# design.net
KiCad netlist of a schematic drawn in Altium Designer
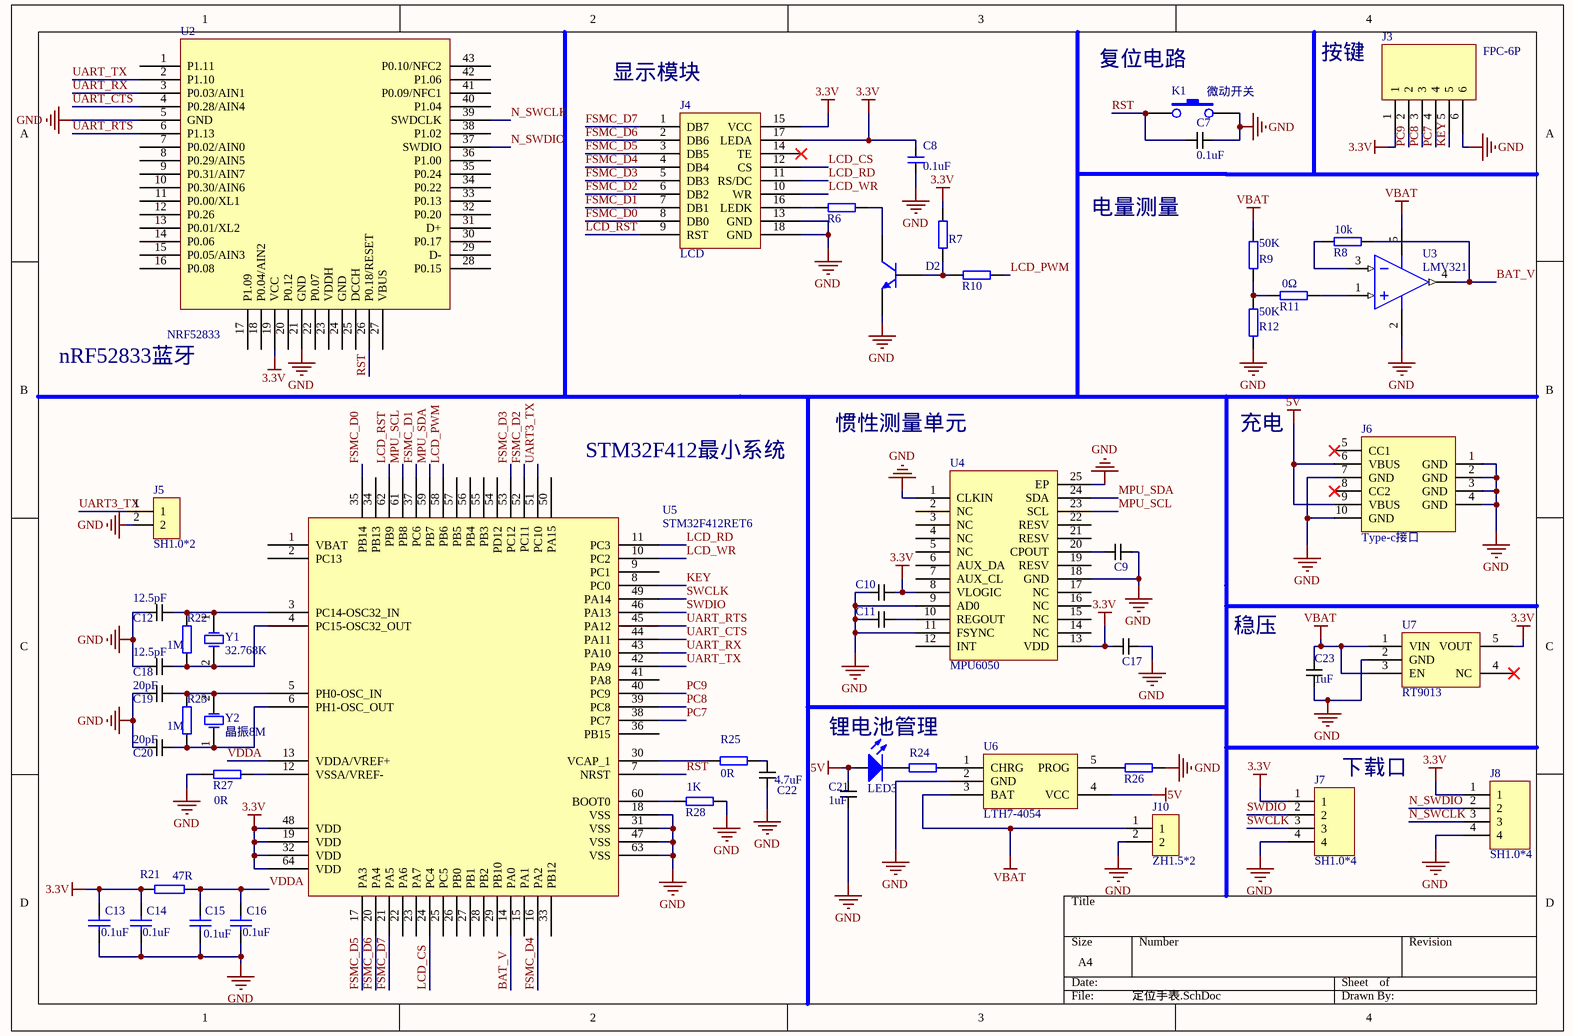
[diagram p0: 定位手表.SchDoc]

(export (version "E")
  (design (tool "Eeschema 10.0.6"))
  (components
    (comp (ref "C7")
      (value "0.1uF")
      (footprint "0402-CAP")
      (description "无极性贴片电容")
      (libsource (lib "定位手表") (part "电容"))
    )
    (comp (ref "C8")
      (value "0.1uF")
      (footprint "0402-CAP")
      (description "无极性贴片电容")
      (libsource (lib "定位手表") (part "电容"))
    )
    (comp (ref "C9")
      (value "2.2nF")
      (footprint "0402-CAP")
      (description "无极性贴片电容")
      (libsource (lib "定位手表") (part "电容"))
    )
    (comp (ref "C10")
      (value "0.1uF")
      (footprint "0402-CAP")
      (description "无极性贴片电容")
      (libsource (lib "定位手表") (part "电容"))
    )
    (comp (ref "C11")
      (value "0.1uF")
      (footprint "0402-CAP")
      (description "无极性贴片电容")
      (libsource (lib "定位手表") (part "电容"))
    )
    (comp (ref "C12")
      (value "12.5pF")
      (footprint "0402-CAP")
      (description "无极性贴片电容")
      (libsource (lib "定位手表") (part "电容"))
    )
    (comp (ref "C13") (value "0.1uF") (footprint "0402-CAP") (libsource (lib "定位手表") (part "cap")))
    (comp (ref "C14") (value "0.1uF") (footprint "0402-CAP") (libsource (lib "定位手表") (part "cap")))
    (comp (ref "C15") (value "0.1uF") (footprint "0402-CAP") (libsource (lib "定位手表") (part "cap")))
    (comp (ref "C16") (value "0.1uF") (footprint "0402-CAP") (libsource (lib "定位手表") (part "cap")))
    (comp (ref "C17")
      (value "0.1uF")
      (footprint "0402-CAP")
      (description "无极性贴片电容")
      (libsource (lib "定位手表") (part "电容"))
    )
    (comp (ref "C18")
      (value "12.5pF")
      (footprint "0402-CAP")
      (description "无极性贴片电容")
      (libsource (lib "定位手表") (part "电容"))
    )
    (comp (ref "C19")
      (value "20pF")
      (footprint "0402-CAP")
      (description "无极性贴片电容")
      (libsource (lib "定位手表") (part "电容"))
    )
    (comp (ref "C20")
      (value "20pF")
      (footprint "0402-CAP")
      (description "无极性贴片电容")
      (libsource (lib "定位手表") (part "电容"))
    )
    (comp (ref "C21")
      (value "1uF")
      (footprint "0402-CAP")
      (description "无极性贴片电容")
      (libsource (lib "定位手表") (part "电容"))
    )
    (comp (ref "C22")
      (value "4.7uF")
      (footprint "0603-CAP")
      (description "无极性贴片电容")
      (libsource (lib "定位手表") (part "电容"))
    )
    (comp (ref "C23")
      (value "1uF")
      (footprint "0402-CAP")
      (description "无极性贴片电容")
      (libsource (lib "定位手表") (part "电容"))
    )
    (comp (ref "D2") (value "三极管") (footprint "SOT23-3M") (libsource (lib "定位手表") (part "三极管")))
    (comp (ref "J3") (value "FPC-6P") (footprint "FPC0.5-WT-6P") (libsource (lib "定位手表") (part "FPC-6P")))
    (comp (ref "J4") (value "LCD") (footprint "LCD") (libsource (lib "定位手表") (part "LCD")))
    (comp (ref "J5") (value "SH1.0*2") (footprint "SH1.0-WT-2P") (libsource (lib "定位手表") (part "SH1.0*2")))
    (comp (ref "J6")
      (value "Type-c接口")
      (footprint "type-c")
      (description "接口")
      (libsource (lib "定位手表") (part "Type-c接口"))
    )
    (comp (ref "J7") (value "SH1.0*4") (footprint "SH1.0-WT-4P") (libsource (lib "定位手表") (part "SH1.0*4")))
    (comp (ref "J8") (value "SH1.0*4") (footprint "SH1.0-WT-4P") (libsource (lib "定位手表") (part "SH1.0*4")))
    (comp (ref "J10") (value "ZH1.5*2") (footprint "ZH1.5-WS-2P") (libsource (lib "定位手表") (part "ZH1.5*2")))
    (comp (ref "K1") (value "微动开关") (footprint "轻触开关") (libsource (lib "定位手表") (part "微动开关")))
    (comp (ref "LED3") (value "发光二极管") (footprint "0603-LED") (libsource (lib "定位手表") (part "发光二极管")))
    (comp (ref "R6")
      (value "10R")
      (footprint "0402-RES")
      (description "电阻")
      (libsource (lib "定位手表") (part "电阻"))
    )
    (comp (ref "R7")
      (value "10K")
      (footprint "0402-RES")
      (description "电阻")
      (libsource (lib "定位手表") (part "电阻"))
    )
    (comp (ref "R8")
      (value "10k")
      (footprint "0402-RES")
      (description "电阻")
      (libsource (lib "智能门锁") (part "电阻"))
    )
    (comp (ref "R9")
      (value "50K")
      (footprint "0402-RES")
      (description "电阻")
      (libsource (lib "智能门锁") (part "电阻"))
    )
    (comp (ref "R10")
      (value "1K")
      (footprint "0402-RES")
      (description "电阻")
      (libsource (lib "定位手表") (part "电阻"))
    )
    (comp (ref "R11")
      (value "0Ω")
      (footprint "0402-RES")
      (description "电阻")
      (libsource (lib "智能门锁") (part "电阻"))
    )
    (comp (ref "R12")
      (value "50K")
      (footprint "0402-RES")
      (description "电阻")
      (libsource (lib "智能门锁") (part "电阻"))
    )
    (comp (ref "R21") (value "47R") (footprint "0402-RES") (libsource (lib "定位手表") (part "RES")))
    (comp (ref "R22")
      (value "1M")
      (footprint "0402-RES")
      (description "电阻")
      (libsource (lib "定位手表") (part "电阻"))
    )
    (comp (ref "R23")
      (value "1M")
      (footprint "0402-RES")
      (description "电阻")
      (libsource (lib "定位手表") (part "电阻"))
    )
    (comp (ref "R24")
      (value "10K")
      (footprint "0402-RES")
      (description "电阻")
      (libsource (lib "定位手表") (part "电阻"))
    )
    (comp (ref "R25")
      (value "0R")
      (footprint "0402-RES")
      (description "电阻")
      (libsource (lib "定位手表") (part "电阻"))
    )
    (comp (ref "R26")
      (value "1.65K")
      (footprint "0402-RES")
      (description "电阻")
      (libsource (lib "定位手表") (part "电阻"))
    )
    (comp (ref "R27")
      (value "0R")
      (footprint "0402-RES")
      (description "电阻")
      (libsource (lib "定位手表") (part "电阻"))
    )
    (comp (ref "R28")
      (value "1K")
      (footprint "0402-RES")
      (description "电阻")
      (libsource (lib "定位手表") (part "电阻"))
    )
    (comp (ref "U2") (value "NRF52833") (footprint "nrf52833") (libsource (lib "定位手表") (part "NRF52833")))
    (comp (ref "U3") (value "LMV321") (footprint "SOT23-5") (libsource (lib "定位手表") (part "LMV321")))
    (comp (ref "U4") (value "MPU6050") (footprint "MPU6050") (libsource (lib "定位手表") (part "MPU6050")))
    (comp (ref "U5")
      (value "STM32F412RET6")
      (footprint "STM32F412RET6")
      (libsource (lib "定位手表") (part "STM32F412RET6"))
    )
    (comp (ref "U6") (value "LTH7-4054") (footprint "SOT23-5") (libsource (lib "定位手表") (part "LTH7-4054")))
    (comp (ref "U7") (value "RT9013") (footprint "SOT23-5") (libsource (lib "定位手表") (part "RT9013")))
    (comp (ref "Y1") (value "32.768K") (footprint "晶振32.768K") (libsource (lib "定位手表") (part "32.768K")))
    (comp (ref "Y2") (value "晶振8M") (footprint "晶振8M") (libsource (lib "定位手表") (part "晶振8M")))
  )
  (nets
    (net (code "1") (name "/BAT_V") (class "Default")
      (node (ref "R8") (pin "2") (pinfunction "2_2") (pintype "passive"))
      (node (ref "U3") (pin "4") (pinfunction "4_4") (pintype "output"))
      (node (ref "U5") (pin "14") (pinfunction "PA0_14") (pintype "passive"))
    )
    (net (code "2") (name "/FSMC_D0") (class "Default")
      (node (ref "J4") (pin "8") (pinfunction "DB0_8") (pintype "passive"))
      (node (ref "U5") (pin "35") (pinfunction "PB14_35") (pintype "passive"))
    )
    (net (code "3") (name "/FSMC_D1") (class "Default")
      (node (ref "J4") (pin "7") (pinfunction "DB1_7") (pintype "passive"))
      (node (ref "U5") (pin "37") (pinfunction "PC6_37") (pintype "passive"))
    )
    (net (code "4") (name "/FSMC_D2") (class "Default")
      (node (ref "J4") (pin "6") (pinfunction "DB2_6") (pintype "passive"))
      (node (ref "U5") (pin "52") (pinfunction "PC11_52") (pintype "passive"))
    )
    (net (code "5") (name "/FSMC_D3") (class "Default")
      (node (ref "J4") (pin "5") (pinfunction "DB3_5") (pintype "passive"))
      (node (ref "U5") (pin "53") (pinfunction "PC12_53") (pintype "passive"))
    )
    (net (code "6") (name "/FSMC_D4") (class "Default")
      (node (ref "J4") (pin "4") (pinfunction "DB4_4") (pintype "passive"))
      (node (ref "U5") (pin "16") (pinfunction "PA2_16") (pintype "passive"))
    )
    (net (code "7") (name "/FSMC_D5") (class "Default")
      (node (ref "J4") (pin "3") (pinfunction "DB5_3") (pintype "passive"))
      (node (ref "U5") (pin "17") (pinfunction "PA3_17") (pintype "passive"))
    )
    (net (code "8") (name "/FSMC_D6") (class "Default")
      (node (ref "J4") (pin "2") (pinfunction "DB6_2") (pintype "passive"))
      (node (ref "U5") (pin "20") (pinfunction "PA4_20") (pintype "passive"))
    )
    (net (code "9") (name "/FSMC_D7") (class "Default")
      (node (ref "J4") (pin "1") (pinfunction "DB7_1") (pintype "passive"))
      (node (ref "U5") (pin "21") (pinfunction "PA5_21") (pintype "passive"))
    )
    (net (code "10") (name "/KEY") (class "Default")
      (node (ref "J3") (pin "5") (pinfunction "5_5") (pintype "passive"))
      (node (ref "U5") (pin "8") (pinfunction "PC0_8") (pintype "passive"))
    )
    (net (code "11") (name "/LCD_CS") (class "Default")
      (node (ref "J4") (pin "12") (pinfunction "CS_12") (pintype "passive"))
      (node (ref "U5") (pin "24") (pinfunction "PC4_24") (pintype "passive"))
    )
    (net (code "12") (name "/LCD_PWM") (class "Default")
      (node (ref "R10") (pin "2") (pinfunction "2_2") (pintype "passive"))
      (node (ref "U5") (pin "58") (pinfunction "PB6_58") (pintype "passive"))
    )
    (net (code "13") (name "/LCD_RD") (class "Default")
      (node (ref "J4") (pin "11") (pinfunction "RS/DC_11") (pintype "passive"))
      (node (ref "U5") (pin "11") (pinfunction "PC3_11") (pintype "passive"))
    )
    (net (code "14") (name "/LCD_RST") (class "Default")
      (node (ref "J4") (pin "9") (pinfunction "RST_9") (pintype "passive"))
      (node (ref "U5") (pin "62") (pinfunction "PB9_62") (pintype "passive"))
    )
    (net (code "15") (name "/LCD_WR") (class "Default")
      (node (ref "J4") (pin "10") (pinfunction "WR_10") (pintype "passive"))
      (node (ref "U5") (pin "10") (pinfunction "PC2_10") (pintype "passive"))
    )
    (net (code "16") (name "/MPU_SCL") (class "Default")
      (node (ref "U4") (pin "23") (pinfunction "SCL_23") (pintype "passive"))
      (node (ref "U5") (pin "61") (pinfunction "PB8_61") (pintype "passive"))
    )
    (net (code "17") (name "/MPU_SDA") (class "Default")
      (node (ref "U4") (pin "24") (pinfunction "SDA_24") (pintype "passive"))
      (node (ref "U5") (pin "59") (pinfunction "PB7_59") (pintype "passive"))
    )
    (net (code "18") (name "/N_SWCLK") (class "Default")
      (node (ref "J8") (pin "3") (pinfunction "3_3") (pintype "passive"))
      (node (ref "U2") (pin "39") (pinfunction "SWDCLK_39") (pintype "passive"))
    )
    (net (code "19") (name "/N_SWDIO") (class "Default")
      (node (ref "J8") (pin "2") (pinfunction "2_2") (pintype "passive"))
      (node (ref "U2") (pin "37") (pinfunction "SWDIO_37") (pintype "passive"))
    )
    (net (code "20") (name "/PC7") (class "Default")
      (node (ref "J3") (pin "4") (pinfunction "4_4") (pintype "passive"))
      (node (ref "U5") (pin "38") (pinfunction "PC7_38") (pintype "passive"))
    )
    (net (code "21") (name "/PC8") (class "Default")
      (node (ref "J3") (pin "3") (pinfunction "3_3") (pintype "passive"))
      (node (ref "U5") (pin "39") (pinfunction "PC8_39") (pintype "passive"))
    )
    (net (code "22") (name "/PC9") (class "Default")
      (node (ref "J3") (pin "2") (pinfunction "2_2") (pintype "passive"))
      (node (ref "U5") (pin "40") (pinfunction "PC9_40") (pintype "passive"))
    )
    (net (code "23") (name "/RST") (class "Default")
      (node (ref "C7") (pin "2") (pintype "passive"))
      (node (ref "K1") (pin "1") (pinfunction "1_1") (pintype "passive"))
      (node (ref "U2") (pin "26") (pinfunction "P0.18/RESET_26") (pintype "passive"))
      (node (ref "U5") (pin "7") (pinfunction "NRST_7") (pintype "passive"))
    )
    (net (code "24") (name "/SWCLK") (class "Default")
      (node (ref "J7") (pin "3") (pinfunction "3_3") (pintype "passive"))
      (node (ref "U5") (pin "49") (pinfunction "PA14_49") (pintype "passive"))
    )
    (net (code "25") (name "/SWDIO") (class "Default")
      (node (ref "J7") (pin "2") (pinfunction "2_2") (pintype "passive"))
      (node (ref "U5") (pin "46") (pinfunction "PA13_46") (pintype "passive"))
    )
    (net (code "26") (name "/UART3_TX") (class "Default")
      (node (ref "J5") (pin "1") (pinfunction "1_1") (pintype "passive"))
      (node (ref "U5") (pin "51") (pinfunction "PC10_51") (pintype "passive"))
    )
    (net (code "27") (name "/UART_CTS") (class "Default")
      (node (ref "U2") (pin "4") (pinfunction "P0.28/AIN4_4") (pintype "passive"))
      (node (ref "U5") (pin "44") (pinfunction "PA11_44") (pintype "passive"))
    )
    (net (code "28") (name "/UART_RTS") (class "Default")
      (node (ref "U2") (pin "6") (pinfunction "P1.13_6") (pintype "passive"))
      (node (ref "U5") (pin "45") (pinfunction "PA12_45") (pintype "passive"))
    )
    (net (code "29") (name "/UART_RX") (class "Default")
      (node (ref "U2") (pin "3") (pinfunction "P0.03/AIN1_3") (pintype "passive"))
      (node (ref "U5") (pin "43") (pinfunction "PA10_43") (pintype "passive"))
    )
    (net (code "30") (name "/UART_TX") (class "Default")
      (node (ref "U2") (pin "2") (pinfunction "P1.10_2") (pintype "passive"))
      (node (ref "U5") (pin "42") (pinfunction "PA9_42") (pintype "passive"))
    )
    (net (code "31") (name "/VDDA") (class "Default")
      (node (ref "C15") (pin "2") (pinfunction "2_2") (pintype "passive"))
      (node (ref "C16") (pin "2") (pinfunction "2_2") (pintype "passive"))
      (node (ref "R21") (pin "2") (pinfunction "2_2") (pintype "passive"))
      (node (ref "U5") (pin "13") (pinfunction "VDDA/VREF+_13") (pintype "passive"))
    )
    (net (code "32") (name "3.3V") (class "Default")
      (node (ref "C10") (pin "2") (pintype "passive"))
      (node (ref "C13") (pin "2") (pinfunction "2_2") (pintype "passive"))
      (node (ref "C14") (pin "2") (pinfunction "2_2") (pintype "passive"))
      (node (ref "C17") (pin "2") (pintype "passive"))
      (node (ref "C8") (pin "1") (pintype "passive"))
      (node (ref "J3") (pin "1") (pinfunction "1_1") (pintype "passive"))
      (node (ref "J4") (pin "15") (pinfunction "VCC_15") (pintype "passive"))
      (node (ref "J4") (pin "17") (pinfunction "LEDA_17") (pintype "passive"))
      (node (ref "J7") (pin "1") (pinfunction "1_1") (pintype "passive"))
      (node (ref "J8") (pin "1") (pinfunction "1_1") (pintype "passive"))
      (node (ref "R21") (pin "1") (pinfunction "1_1") (pintype "passive"))
      (node (ref "R7") (pin "2") (pinfunction "2_2") (pintype "passive"))
      (node (ref "U2") (pin "19") (pinfunction "VCC_19") (pintype "passive"))
      (node (ref "U4") (pin "13") (pinfunction "VDD_13") (pintype "passive"))
      (node (ref "U4") (pin "8") (pinfunction "VLOGIC_8") (pintype "passive"))
      (node (ref "U5") (pin "19") (pinfunction "VDD_19") (pintype "passive"))
      (node (ref "U5") (pin "32") (pinfunction "VDD_32") (pintype "passive"))
      (node (ref "U5") (pin "48") (pinfunction "VDD_48") (pintype "passive"))
      (node (ref "U5") (pin "64") (pinfunction "VDD_64") (pintype "passive"))
      (node (ref "U7") (pin "5") (pinfunction "VOUT_5") (pintype "passive"))
    )
    (net (code "33") (name "5V") (class "Default")
      (node (ref "C21") (pin "1") (pintype "passive"))
      (node (ref "J6") (pin "6") (pinfunction "VBUS_6") (pintype "passive"))
      (node (ref "J6") (pin "9") (pinfunction "VBUS_9") (pintype "passive"))
      (node (ref "LED3") (pin "1") (pinfunction "1_1") (pintype "passive"))
      (node (ref "U6") (pin "4") (pinfunction "VCC_4") (pintype "passive"))
    )
    (net (code "34") (name "GND") (class "Default")
      (node (ref "C10") (pin "1") (pintype "passive"))
      (node (ref "C11") (pin "1") (pintype "passive"))
      (node (ref "C12") (pin "1") (pintype "passive"))
      (node (ref "C13") (pin "1") (pinfunction "1_1") (pintype "passive"))
      (node (ref "C14") (pin "1") (pinfunction "1_1") (pintype "passive"))
      (node (ref "C15") (pin "1") (pinfunction "1_1") (pintype "passive"))
      (node (ref "C16") (pin "1") (pinfunction "1_1") (pintype "passive"))
      (node (ref "C17") (pin "1") (pintype "passive"))
      (node (ref "C18") (pin "1") (pintype "passive"))
      (node (ref "C19") (pin "1") (pintype "passive"))
      (node (ref "C20") (pin "1") (pintype "passive"))
      (node (ref "C21") (pin "2") (pintype "passive"))
      (node (ref "C22") (pin "1") (pintype "passive"))
      (node (ref "C23") (pin "2") (pintype "passive"))
      (node (ref "C7") (pin "1") (pintype "passive"))
      (node (ref "C8") (pin "2") (pintype "passive"))
      (node (ref "C9") (pin "2") (pintype "passive"))
      (node (ref "D2") (pin "2") (pinfunction "E_2") (pintype "passive"))
      (node (ref "J10") (pin "2") (pinfunction "2_2") (pintype "passive"))
      (node (ref "J3") (pin "6") (pinfunction "6_6") (pintype "passive"))
      (node (ref "J4") (pin "13") (pinfunction "GND_13") (pintype "passive"))
      (node (ref "J4") (pin "18") (pinfunction "GND_18") (pintype "passive"))
      (node (ref "J5") (pin "2") (pinfunction "2_2") (pintype "passive"))
      (node (ref "J6") (pin "1") (pinfunction "GND_1") (pintype "passive"))
      (node (ref "J6") (pin "10") (pinfunction "GND_10") (pintype "passive"))
      (node (ref "J6") (pin "2") (pinfunction "GND_2") (pintype "passive"))
      (node (ref "J6") (pin "3") (pinfunction "GND_3") (pintype "passive"))
      (node (ref "J6") (pin "4") (pinfunction "GND_4") (pintype "passive"))
      (node (ref "J6") (pin "7") (pinfunction "GND_7") (pintype "passive"))
      (node (ref "J7") (pin "4") (pinfunction "4_4") (pintype "passive"))
      (node (ref "J8") (pin "4") (pinfunction "4_4") (pintype "passive"))
      (node (ref "K1") (pin "2") (pinfunction "2_2") (pintype "passive"))
      (node (ref "R12") (pin "2") (pinfunction "2_2") (pintype "passive"))
      (node (ref "R26") (pin "2") (pinfunction "2_2") (pintype "passive"))
      (node (ref "R27") (pin "1") (pinfunction "1_1") (pintype "passive"))
      (node (ref "R28") (pin "2") (pinfunction "2_2") (pintype "passive"))
      (node (ref "U2") (pin "21") (pinfunction "GND_21") (pintype "passive"))
      (node (ref "U2") (pin "5") (pinfunction "GND_5") (pintype "passive"))
      (node (ref "U3") (pin "2") (pinfunction "2_2") (pintype "power_in"))
      (node (ref "U4") (pin "1") (pinfunction "CLKIN_1") (pintype "passive"))
      (node (ref "U4") (pin "11") (pinfunction "FSYNC_11") (pintype "passive"))
      (node (ref "U4") (pin "18") (pinfunction "GND_18") (pintype "passive"))
      (node (ref "U4") (pin "25") (pinfunction "EP_25") (pintype "passive"))
      (node (ref "U4") (pin "9") (pinfunction "AD0_9") (pintype "passive"))
      (node (ref "U5") (pin "18") (pinfunction "VSS_18") (pintype "passive"))
      (node (ref "U5") (pin "31") (pinfunction "VSS_31") (pintype "passive"))
      (node (ref "U5") (pin "47") (pinfunction "VSS_47") (pintype "passive"))
      (node (ref "U5") (pin "63") (pinfunction "VSS_63") (pintype "passive"))
      (node (ref "U6") (pin "2") (pinfunction "GND_2") (pintype "passive"))
      (node (ref "U7") (pin "2") (pinfunction "GND_2") (pintype "passive"))
    )
    (net (code "35") (name "Net-(C22-Pad2)") (class "Default")
      (node (ref "C22") (pin "2") (pintype "passive"))
      (node (ref "R25") (pin "2") (pinfunction "2_2") (pintype "passive"))
    )
    (net (code "36") (name "Net-(D2-B)") (class "Default")
      (node (ref "D2") (pin "1") (pinfunction "B_1") (pintype "passive"))
      (node (ref "R10") (pin "1") (pinfunction "1_1") (pintype "passive"))
      (node (ref "R7") (pin "1") (pinfunction "1_1") (pintype "passive"))
    )
    (net (code "37") (name "Net-(D2-C)") (class "Default")
      (node (ref "D2") (pin "3") (pinfunction "C_3") (pintype "passive"))
      (node (ref "R6") (pin "2") (pinfunction "2_2") (pintype "passive"))
    )
    (net (code "38") (name "Net-(J4-LEDK)") (class "Default")
      (node (ref "J4") (pin "16") (pinfunction "LEDK_16") (pintype "passive"))
      (node (ref "R6") (pin "1") (pinfunction "1_1") (pintype "passive"))
    )
    (net (code "39") (name "Net-(LED3-Pad2)") (class "Default")
      (node (ref "LED3") (pin "2") (pinfunction "2_2") (pintype "passive"))
      (node (ref "R24") (pin "1") (pinfunction "1_1") (pintype "passive"))
    )
    (net (code "40") (name "Net-(R8-Pad1)") (class "Default")
      (node (ref "R8") (pin "1") (pinfunction "1_1") (pintype "passive"))
      (node (ref "U3") (pin "3") (pinfunction "3_3") (pintype "input"))
    )
    (net (code "41") (name "Net-(R11-Pad1)") (class "Default")
      (node (ref "R11") (pin "1") (pinfunction "1_1") (pintype "passive"))
      (node (ref "R12") (pin "1") (pinfunction "1_1") (pintype "passive"))
      (node (ref "R9") (pin "2") (pinfunction "2_2") (pintype "passive"))
    )
    (net (code "42") (name "Net-(R11-Pad2)") (class "Default")
      (node (ref "R11") (pin "2") (pinfunction "2_2") (pintype "passive"))
      (node (ref "U3") (pin "1") (pinfunction "1_1") (pintype "input"))
    )
    (net (code "43") (name "Net-(U4-CPOUT)") (class "Default")
      (node (ref "C9") (pin "1") (pintype "passive"))
      (node (ref "U4") (pin "20") (pinfunction "CPOUT_20") (pintype "passive"))
    )
    (net (code "44") (name "Net-(U4-REGOUT)") (class "Default")
      (node (ref "C11") (pin "2") (pintype "passive"))
      (node (ref "U4") (pin "10") (pinfunction "REGOUT_10") (pintype "passive"))
    )
    (net (code "45") (name "Net-(U5-BOOT0)") (class "Default")
      (node (ref "R28") (pin "1") (pinfunction "1_1") (pintype "passive"))
      (node (ref "U5") (pin "60") (pinfunction "BOOT0_60") (pintype "passive"))
    )
    (net (code "46") (name "Net-(U5-PC14-OSC32_IN)") (class "Default")
      (node (ref "C12") (pin "2") (pintype "passive"))
      (node (ref "R22") (pin "1") (pinfunction "1_1") (pintype "passive"))
      (node (ref "U5") (pin "3") (pinfunction "PC14-OSC32_IN_3") (pintype "passive"))
      (node (ref "Y1") (pin "1") (pinfunction "OSC1_1") (pintype "passive"))
    )
    (net (code "47") (name "Net-(U5-PC15-OSC32_OUT)") (class "Default")
      (node (ref "C18") (pin "2") (pintype "passive"))
      (node (ref "R22") (pin "2") (pinfunction "2_2") (pintype "passive"))
      (node (ref "U5") (pin "4") (pinfunction "PC15-OSC32_OUT_4") (pintype "passive"))
      (node (ref "Y1") (pin "2") (pinfunction "OSC2_2") (pintype "passive"))
    )
    (net (code "48") (name "Net-(U5-PH0-OSC_IN)") (class "Default")
      (node (ref "C19") (pin "2") (pintype "passive"))
      (node (ref "R23") (pin "1") (pinfunction "1_1") (pintype "passive"))
      (node (ref "U5") (pin "5") (pinfunction "PH0-OSC_IN_5") (pintype "passive"))
      (node (ref "Y2") (pin "2") (pinfunction "OSC2_2") (pintype "passive"))
    )
    (net (code "49") (name "Net-(U5-PH1-OSC_OUT)") (class "Default")
      (node (ref "C20") (pin "2") (pintype "passive"))
      (node (ref "R23") (pin "2") (pinfunction "2_2") (pintype "passive"))
      (node (ref "U5") (pin "6") (pinfunction "PH1-OSC_OUT_6") (pintype "passive"))
      (node (ref "Y2") (pin "1") (pinfunction "OSC1_1") (pintype "passive"))
    )
    (net (code "50") (name "Net-(U5-VCAP_1)") (class "Default")
      (node (ref "R25") (pin "1") (pinfunction "1_1") (pintype "passive"))
      (node (ref "U5") (pin "30") (pinfunction "VCAP_1_30") (pintype "passive"))
    )
    (net (code "51") (name "Net-(U5-VSSA{slash}VREF-)") (class "Default")
      (node (ref "R27") (pin "2") (pinfunction "2_2") (pintype "passive"))
      (node (ref "U5") (pin "12") (pinfunction "VSSA/VREF-_12") (pintype "passive"))
    )
    (net (code "52") (name "Net-(U6-CHRG)") (class "Default")
      (node (ref "R24") (pin "2") (pinfunction "2_2") (pintype "passive"))
      (node (ref "U6") (pin "1") (pinfunction "CHRG_1") (pintype "passive"))
    )
    (net (code "53") (name "Net-(U6-PROG)") (class "Default")
      (node (ref "R26") (pin "1") (pinfunction "1_1") (pintype "passive"))
      (node (ref "U6") (pin "5") (pinfunction "PROG_5") (pintype "passive"))
    )
    (net (code "54") (name "VBAT") (class "Default")
      (node (ref "C23") (pin "1") (pintype "passive"))
      (node (ref "J10") (pin "1") (pinfunction "1_1") (pintype "passive"))
      (node (ref "R9") (pin "1") (pinfunction "1_1") (pintype "passive"))
      (node (ref "U3") (pin "5") (pinfunction "5_5") (pintype "power_in"))
      (node (ref "U6") (pin "3") (pinfunction "BAT_3") (pintype "passive"))
      (node (ref "U7") (pin "1") (pinfunction "VIN_1") (pintype "passive"))
      (node (ref "U7") (pin "3") (pinfunction "EN_3") (pintype "passive"))
    )
    (net (code "55") (name "unconnected-(J4-TE-Pad14)") (class "Default")
      (node (ref "J4") (pin "14") (pinfunction "TE_14") (pintype "passive+no_connect"))
    )
    (net (code "56") (name "unconnected-(J6-CC1-Pad5)") (class "Default")
      (node (ref "J6") (pin "5") (pinfunction "CC1_5") (pintype "passive+no_connect"))
    )
    (net (code "57") (name "unconnected-(J6-CC2-Pad8)") (class "Default")
      (node (ref "J6") (pin "8") (pinfunction "CC2_8") (pintype "passive+no_connect"))
    )
    (net (code "58") (name "unconnected-(U2-D+-Pad31)") (class "Default")
      (node (ref "U2") (pin "31") (pinfunction "D+_31") (pintype "passive"))
    )
    (net (code "59") (name "unconnected-(U2-D--Pad29)") (class "Default")
      (node (ref "U2") (pin "29") (pinfunction "D-_29") (pintype "passive"))
    )
    (net (code "60") (name "unconnected-(U2-DCCH-Pad25)") (class "Default")
      (node (ref "U2") (pin "25") (pinfunction "DCCH_25") (pintype "passive"))
    )
    (net (code "61") (name "unconnected-(U2-GND-Pad24)") (class "Default")
      (node (ref "U2") (pin "24") (pinfunction "GND_24") (pintype "passive"))
    )
    (net (code "62") (name "unconnected-(U2-P0.00{slash}XL1-Pad11)") (class "Default")
      (node (ref "U2") (pin "11") (pinfunction "P0.00/XL1_11") (pintype "passive"))
    )
    (net (code "63") (name "unconnected-(U2-P0.01{slash}XL2-Pad13)") (class "Default")
      (node (ref "U2") (pin "13") (pinfunction "P0.01/XL2_13") (pintype "passive"))
    )
    (net (code "64") (name "unconnected-(U2-P0.02{slash}AIN0-Pad7)") (class "Default")
      (node (ref "U2") (pin "7") (pinfunction "P0.02/AIN0_7") (pintype "passive"))
    )
    (net (code "65") (name "unconnected-(U2-P0.04{slash}AIN2-Pad18)") (class "Default")
      (node (ref "U2") (pin "18") (pinfunction "P0.04/AIN2_18") (pintype "passive"))
    )
    (net (code "66") (name "unconnected-(U2-P0.05{slash}AIN3-Pad15)") (class "Default")
      (node (ref "U2") (pin "15") (pinfunction "P0.05/AIN3_15") (pintype "passive"))
    )
    (net (code "67") (name "unconnected-(U2-P0.06-Pad14)") (class "Default")
      (node (ref "U2") (pin "14") (pinfunction "P0.06_14") (pintype "passive"))
    )
    (net (code "68") (name "unconnected-(U2-P0.07-Pad22)") (class "Default")
      (node (ref "U2") (pin "22") (pinfunction "P0.07_22") (pintype "passive"))
    )
    (net (code "69") (name "unconnected-(U2-P0.08-Pad16)") (class "Default")
      (node (ref "U2") (pin "16") (pinfunction "P0.08_16") (pintype "passive"))
    )
    (net (code "70") (name "unconnected-(U2-P0.09{slash}NFC1-Pad41)") (class "Default")
      (node (ref "U2") (pin "41") (pinfunction "P0.09/NFC1_41") (pintype "passive"))
    )
    (net (code "71") (name "unconnected-(U2-P0.10{slash}NFC2-Pad43)") (class "Default")
      (node (ref "U2") (pin "43") (pinfunction "P0.10/NFC2_43") (pintype "passive"))
    )
    (net (code "72") (name "unconnected-(U2-P0.12-Pad20)") (class "Default")
      (node (ref "U2") (pin "20") (pinfunction "P0.12_20") (pintype "passive"))
    )
    (net (code "73") (name "unconnected-(U2-P0.13-Pad33)") (class "Default")
      (node (ref "U2") (pin "33") (pinfunction "P0.13_33") (pintype "passive"))
    )
    (net (code "74") (name "unconnected-(U2-P0.15-Pad28)") (class "Default")
      (node (ref "U2") (pin "28") (pinfunction "P0.15_28") (pintype "passive"))
    )
    (net (code "75") (name "unconnected-(U2-P0.17-Pad30)") (class "Default")
      (node (ref "U2") (pin "30") (pinfunction "P0.17_30") (pintype "passive"))
    )
    (net (code "76") (name "unconnected-(U2-P0.20-Pad32)") (class "Default")
      (node (ref "U2") (pin "32") (pinfunction "P0.20_32") (pintype "passive"))
    )
    (net (code "77") (name "unconnected-(U2-P0.22-Pad34)") (class "Default")
      (node (ref "U2") (pin "34") (pinfunction "P0.22_34") (pintype "passive"))
    )
    (net (code "78") (name "unconnected-(U2-P0.24-Pad35)") (class "Default")
      (node (ref "U2") (pin "35") (pinfunction "P0.24_35") (pintype "passive"))
    )
    (net (code "79") (name "unconnected-(U2-P0.26-Pad12)") (class "Default")
      (node (ref "U2") (pin "12") (pinfunction "P0.26_12") (pintype "passive"))
    )
    (net (code "80") (name "unconnected-(U2-P0.29{slash}AIN5-Pad8)") (class "Default")
      (node (ref "U2") (pin "8") (pinfunction "P0.29/AIN5_8") (pintype "passive"))
    )
    (net (code "81") (name "unconnected-(U2-P0.30{slash}AIN6-Pad10)") (class "Default")
      (node (ref "U2") (pin "10") (pinfunction "P0.30/AIN6_10") (pintype "passive"))
    )
    (net (code "82") (name "unconnected-(U2-P0.31{slash}AIN7-Pad9)") (class "Default")
      (node (ref "U2") (pin "9") (pinfunction "P0.31/AIN7_9") (pintype "passive"))
    )
    (net (code "83") (name "unconnected-(U2-P1.00-Pad36)") (class "Default")
      (node (ref "U2") (pin "36") (pinfunction "P1.00_36") (pintype "passive"))
    )
    (net (code "84") (name "unconnected-(U2-P1.02-Pad38)") (class "Default")
      (node (ref "U2") (pin "38") (pinfunction "P1.02_38") (pintype "passive"))
    )
    (net (code "85") (name "unconnected-(U2-P1.04-Pad40)") (class "Default")
      (node (ref "U2") (pin "40") (pinfunction "P1.04_40") (pintype "passive"))
    )
    (net (code "86") (name "unconnected-(U2-P1.06-Pad42)") (class "Default")
      (node (ref "U2") (pin "42") (pinfunction "P1.06_42") (pintype "passive"))
    )
    (net (code "87") (name "unconnected-(U2-P1.09-Pad17)") (class "Default")
      (node (ref "U2") (pin "17") (pinfunction "P1.09_17") (pintype "passive"))
    )
    (net (code "88") (name "unconnected-(U2-P1.11-Pad1)") (class "Default")
      (node (ref "U2") (pin "1") (pinfunction "P1.11_1") (pintype "passive"))
    )
    (net (code "89") (name "unconnected-(U2-VBUS-Pad27)") (class "Default")
      (node (ref "U2") (pin "27") (pinfunction "VBUS_27") (pintype "passive"))
    )
    (net (code "90") (name "unconnected-(U2-VDDH-Pad23)") (class "Default")
      (node (ref "U2") (pin "23") (pinfunction "VDDH_23") (pintype "passive"))
    )
    (net (code "91") (name "unconnected-(U4-AUX_CL-Pad7)") (class "Default")
      (node (ref "U4") (pin "7") (pinfunction "AUX_CL_7") (pintype "passive"))
    )
    (net (code "92") (name "unconnected-(U4-AUX_DA-Pad6)") (class "Default")
      (node (ref "U4") (pin "6") (pinfunction "AUX_DA_6") (pintype "passive"))
    )
    (net (code "93") (name "unconnected-(U4-INT-Pad12)") (class "Default")
      (node (ref "U4") (pin "12") (pinfunction "INT_12") (pintype "passive"))
    )
    (net (code "94") (name "unconnected-(U4-NC-Pad2)") (class "Default")
      (node (ref "U4") (pin "2") (pinfunction "NC_2") (pintype "passive"))
    )
    (net (code "95") (name "unconnected-(U4-NC-Pad3)") (class "Default")
      (node (ref "U4") (pin "3") (pinfunction "NC_3") (pintype "passive"))
    )
    (net (code "96") (name "unconnected-(U4-NC-Pad4)") (class "Default")
      (node (ref "U4") (pin "4") (pinfunction "NC_4") (pintype "passive"))
    )
    (net (code "97") (name "unconnected-(U4-NC-Pad5)") (class "Default")
      (node (ref "U4") (pin "5") (pinfunction "NC_5") (pintype "passive"))
    )
    (net (code "98") (name "unconnected-(U4-NC-Pad14)") (class "Default")
      (node (ref "U4") (pin "14") (pinfunction "NC_14") (pintype "passive"))
    )
    (net (code "99") (name "unconnected-(U4-NC-Pad15)") (class "Default")
      (node (ref "U4") (pin "15") (pinfunction "NC_15") (pintype "passive"))
    )
    (net (code "100") (name "unconnected-(U4-NC-Pad16)") (class "Default")
      (node (ref "U4") (pin "16") (pinfunction "NC_16") (pintype "passive"))
    )
    (net (code "101") (name "unconnected-(U4-NC-Pad17)") (class "Default")
      (node (ref "U4") (pin "17") (pinfunction "NC_17") (pintype "passive"))
    )
    (net (code "102") (name "unconnected-(U4-RESV-Pad19)") (class "Default")
      (node (ref "U4") (pin "19") (pinfunction "RESV_19") (pintype "passive"))
    )
    (net (code "103") (name "unconnected-(U4-RESV-Pad21)") (class "Default")
      (node (ref "U4") (pin "21") (pinfunction "RESV_21") (pintype "passive"))
    )
    (net (code "104") (name "unconnected-(U4-RESV-Pad22)") (class "Default")
      (node (ref "U4") (pin "22") (pinfunction "RESV_22") (pintype "passive"))
    )
    (net (code "105") (name "unconnected-(U5-PA1-Pad15)") (class "Default")
      (node (ref "U5") (pin "15") (pinfunction "PA1_15") (pintype "passive"))
    )
    (net (code "106") (name "unconnected-(U5-PA6-Pad22)") (class "Default")
      (node (ref "U5") (pin "22") (pinfunction "PA6_22") (pintype "passive"))
    )
    (net (code "107") (name "unconnected-(U5-PA7-Pad23)") (class "Default")
      (node (ref "U5") (pin "23") (pinfunction "PA7_23") (pintype "passive"))
    )
    (net (code "108") (name "unconnected-(U5-PA8-Pad41)") (class "Default")
      (node (ref "U5") (pin "41") (pinfunction "PA8_41") (pintype "passive"))
    )
    (net (code "109") (name "unconnected-(U5-PA15-Pad50)") (class "Default")
      (node (ref "U5") (pin "50") (pinfunction "PA15_50") (pintype "passive"))
    )
    (net (code "110") (name "unconnected-(U5-PB0-Pad26)") (class "Default")
      (node (ref "U5") (pin "26") (pinfunction "PB0_26") (pintype "passive"))
    )
    (net (code "111") (name "unconnected-(U5-PB1-Pad27)") (class "Default")
      (node (ref "U5") (pin "27") (pinfunction "PB1_27") (pintype "passive"))
    )
    (net (code "112") (name "unconnected-(U5-PB2-Pad28)") (class "Default")
      (node (ref "U5") (pin "28") (pinfunction "PB2_28") (pintype "passive"))
    )
    (net (code "113") (name "unconnected-(U5-PB3-Pad55)") (class "Default")
      (node (ref "U5") (pin "55") (pinfunction "PB3_55") (pintype "passive"))
    )
    (net (code "114") (name "unconnected-(U5-PB4-Pad56)") (class "Default")
      (node (ref "U5") (pin "56") (pinfunction "PB4_56") (pintype "passive"))
    )
    (net (code "115") (name "unconnected-(U5-PB5-Pad57)") (class "Default")
      (node (ref "U5") (pin "57") (pinfunction "PB5_57") (pintype "passive"))
    )
    (net (code "116") (name "unconnected-(U5-PB10-Pad29)") (class "Default")
      (node (ref "U5") (pin "29") (pinfunction "PB10_29") (pintype "passive"))
    )
    (net (code "117") (name "unconnected-(U5-PB12-Pad33)") (class "Default")
      (node (ref "U5") (pin "33") (pinfunction "PB12_33") (pintype "passive"))
    )
    (net (code "118") (name "unconnected-(U5-PB13-Pad34)") (class "Default")
      (node (ref "U5") (pin "34") (pinfunction "PB13_34") (pintype "passive"))
    )
    (net (code "119") (name "unconnected-(U5-PB15-Pad36)") (class "Default")
      (node (ref "U5") (pin "36") (pinfunction "PB15_36") (pintype "passive"))
    )
    (net (code "120") (name "unconnected-(U5-PC1-Pad9)") (class "Default")
      (node (ref "U5") (pin "9") (pinfunction "PC1_9") (pintype "passive"))
    )
    (net (code "121") (name "unconnected-(U5-PC5-Pad25)") (class "Default")
      (node (ref "U5") (pin "25") (pinfunction "PC5_25") (pintype "passive"))
    )
    (net (code "122") (name "unconnected-(U5-PC13-Pad2)") (class "Default")
      (node (ref "U5") (pin "2") (pinfunction "PC13_2") (pintype "passive"))
    )
    (net (code "123") (name "unconnected-(U5-PD12-Pad54)") (class "Default")
      (node (ref "U5") (pin "54") (pinfunction "PD12_54") (pintype "passive"))
    )
    (net (code "124") (name "unconnected-(U5-VBAT-Pad1)") (class "Default")
      (node (ref "U5") (pin "1") (pinfunction "VBAT_1") (pintype "passive"))
    )
    (net (code "125") (name "unconnected-(U7-NC-Pad4)") (class "Default")
      (node (ref "U7") (pin "4") (pinfunction "NC_4") (pintype "passive+no_connect"))
    )
  )
)
